# LSM303_breakout_board-v12.net
KiCad netlist of a schematic drawn in EAGLE
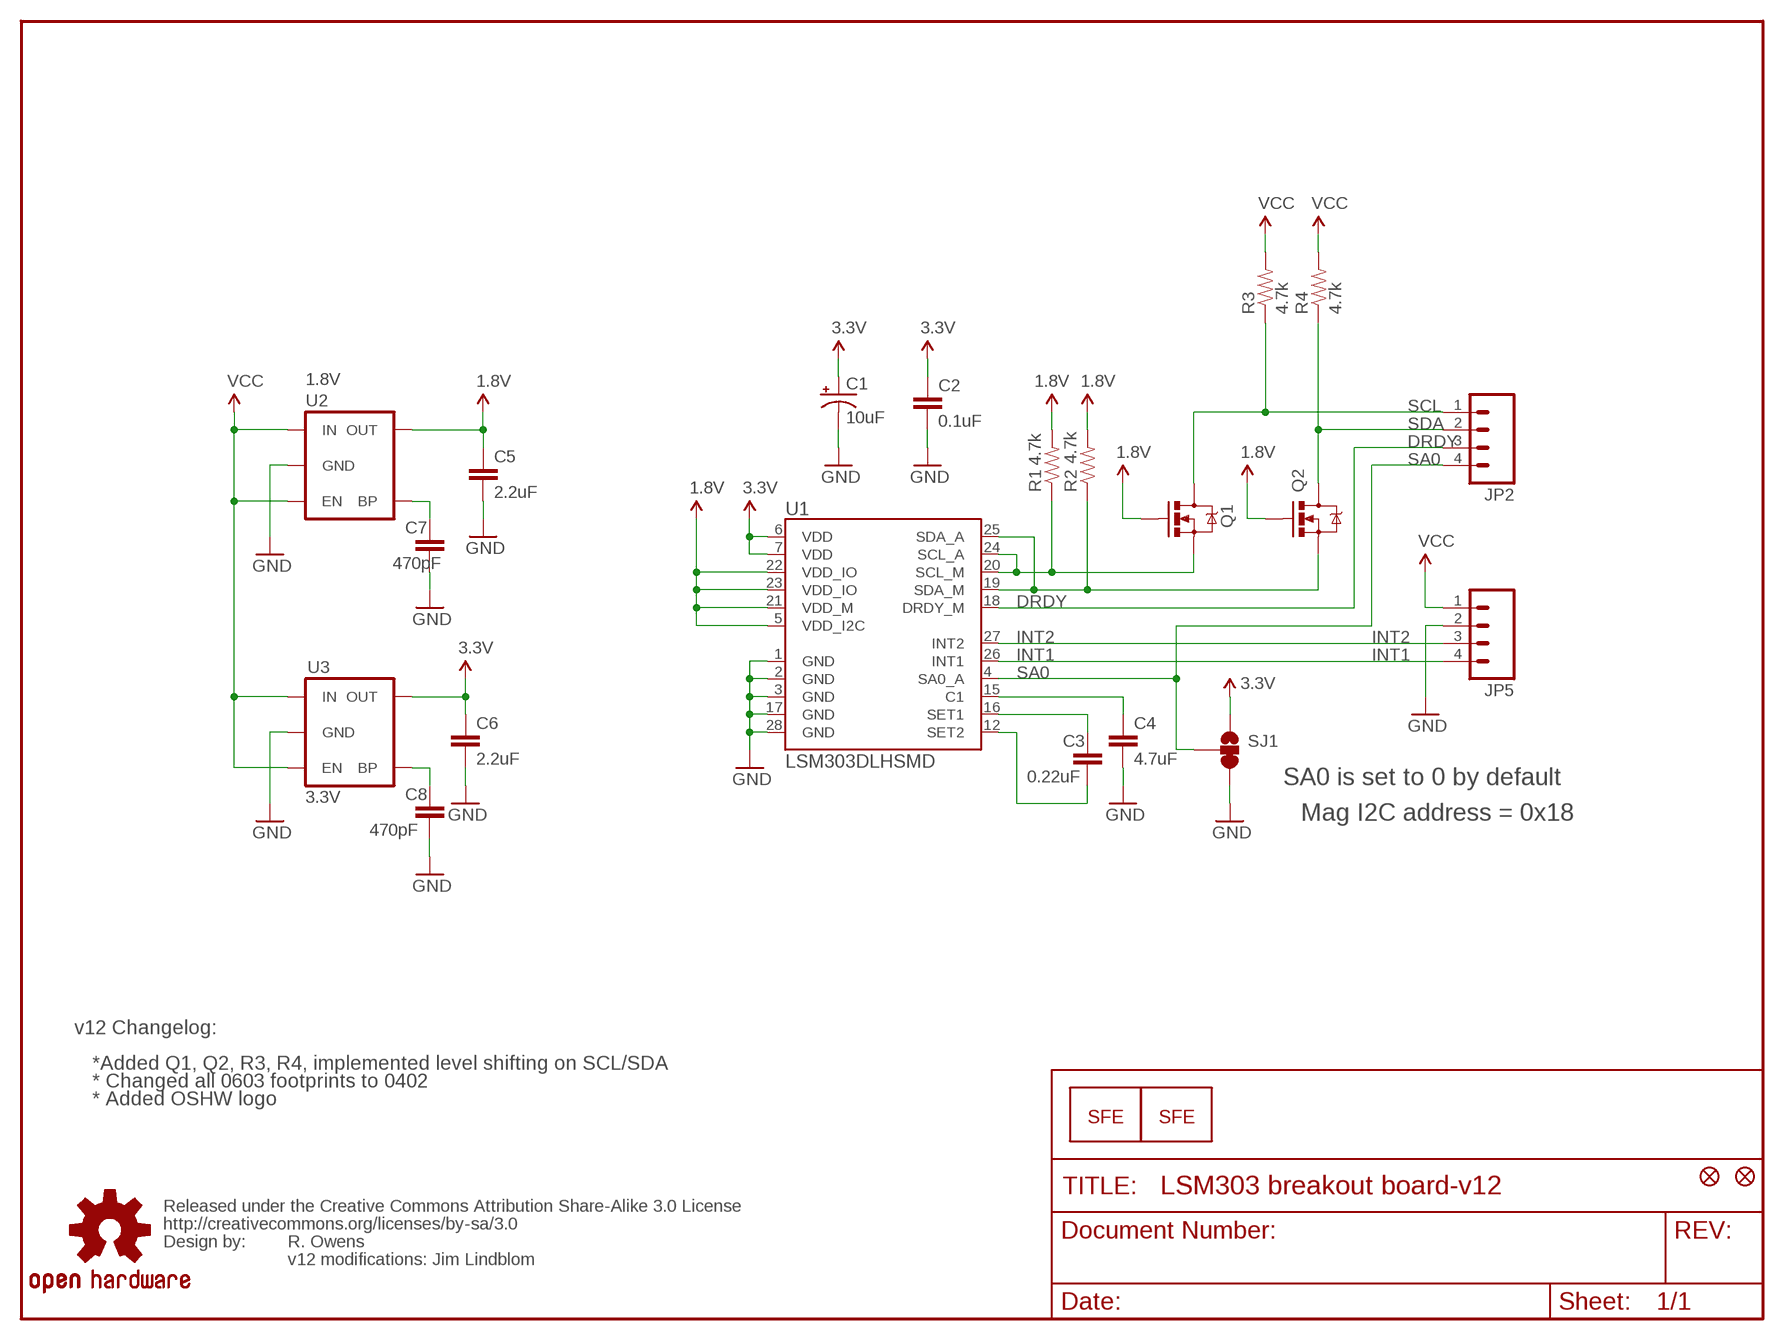
[diagram p0: schematic, sheet 1]

(export (version "E")
  (design (tool "Eeschema 10.0.6"))
  (components
    (comp (ref "C1")
      (value "10uF")
      (footprint "eagle-import:EIA3216")
      (libsource (lib "eagle-import") (part "CAP_POL1206"))
    )
    (comp (ref "C2")
      (value "0.1uF")
      (footprint "eagle-import:0402-CAP")
      (libsource (lib "eagle-import") (part "CAP0402-CAP"))
    )
    (comp (ref "C3")
      (value "0.22uF")
      (footprint "eagle-import:0402-CAP")
      (libsource (lib "eagle-import") (part "CAP0402-CAP"))
    )
    (comp (ref "C4")
      (value "4.7uF")
      (footprint "eagle-import:0402-CAP")
      (libsource (lib "eagle-import") (part "CAP0402-CAP"))
    )
    (comp (ref "C5")
      (value "2.2uF")
      (footprint "eagle-import:0402-CAP")
      (libsource (lib "eagle-import") (part "CAP0402-CAP"))
    )
    (comp (ref "C6")
      (value "2.2uF")
      (footprint "eagle-import:0402-CAP")
      (libsource (lib "eagle-import") (part "CAP0402-CAP"))
    )
    (comp (ref "C7")
      (value "470pF")
      (footprint "eagle-import:0402-CAP")
      (libsource (lib "eagle-import") (part "CAP0402-CAP"))
    )
    (comp (ref "C8")
      (value "470pF")
      (footprint "eagle-import:0402-CAP")
      (libsource (lib "eagle-import") (part "CAP0402-CAP"))
    )
    (comp (ref "JP1")
      (value "LOGO-SFENW2")
      (footprint "eagle-import:SFE-NEW-WEB")
      (libsource (lib "eagle-import") (part "LOGO-SFENW2"))
    )
    (comp (ref "JP2")
      (value "M04PTH")
      (footprint "eagle-import:1X04")
      (libsource (lib "eagle-import") (part "M04PTH"))
    )
    (comp (ref "JP3")
      (value "FIDUCIAL1X2")
      (footprint "eagle-import:FIDUCIAL-1X2")
      (libsource (lib "eagle-import") (part "FIDUCIAL1X2"))
    )
    (comp (ref "JP4")
      (value "FIDUCIAL1X2")
      (footprint "eagle-import:FIDUCIAL-1X2")
      (libsource (lib "eagle-import") (part "FIDUCIAL1X2"))
    )
    (comp (ref "JP5")
      (value "M04PTH")
      (footprint "eagle-import:1X04")
      (libsource (lib "eagle-import") (part "M04PTH"))
    )
    (comp (ref "JP6")
      (value "LOGO-SFESK")
      (footprint "eagle-import:SFE-LOGO-FLAME")
      (libsource (lib "eagle-import") (part "LOGO-SFESK"))
    )
    (comp (ref "Q1")
      (value "MOSFET-N-CH")
      (footprint "eagle-import:SOT23-3")
      (libsource (lib "eagle-import") (part "MOSFET-NCHANNELSMD"))
    )
    (comp (ref "Q2")
      (value "MOSFET-N-CH")
      (footprint "eagle-import:SOT23-3")
      (libsource (lib "eagle-import") (part "MOSFET-NCHANNELSMD"))
    )
    (comp (ref "R1")
      (value "4.7k")
      (footprint "eagle-import:0402-RES")
      (libsource (lib "eagle-import") (part "RESISTOR0402-RES"))
    )
    (comp (ref "R2")
      (value "4.7k")
      (footprint "eagle-import:0402-RES")
      (libsource (lib "eagle-import") (part "RESISTOR0402-RES"))
    )
    (comp (ref "R3")
      (value "4.7k")
      (footprint "eagle-import:0402-RES")
      (libsource (lib "eagle-import") (part "RESISTOR0402-RES"))
    )
    (comp (ref "R4")
      (value "4.7k")
      (footprint "eagle-import:0402-RES")
      (libsource (lib "eagle-import") (part "RESISTOR0402-RES"))
    )
    (comp (ref "SJ1")
      (value "SOLDERJUMPER_2WAYPASTE2&3")
      (footprint "eagle-import:SJ_3_PASTE2&3")
      (libsource (lib "eagle-import") (part "SOLDERJUMPER_2WAYPASTE2&3"))
    )
    (comp (ref "U$5")
      (value "CREATIVE_COMMONS")
      (footprint "eagle-import:CREATIVE_COMMONS")
      (libsource (lib "eagle-import") (part "CREATIVE_COMMONS"))
    )
    (comp (ref "U$8")
      (value "OSHW-LOGOS")
      (footprint "eagle-import:OSHW-LOGO-S")
      (libsource (lib "eagle-import") (part "OSHW-LOGOS"))
    )
    (comp (ref "U1")
      (value "LSM303DLHSMD")
      (footprint "eagle-import:LGA28-5X5")
      (libsource (lib "eagle-import") (part "LSM303DLHSMD"))
    )
    (comp (ref "U2")
      (value "1.8V")
      (footprint "eagle-import:SC70")
      (libsource (lib "eagle-import") (part "V_REG_LDOSMD2"))
    )
    (comp (ref "U3")
      (value "3.3V")
      (footprint "eagle-import:SOT23-5")
      (libsource (lib "eagle-import") (part "V_REG_LDOSMD"))
    )
  )
  (nets
    (net (code "1") (name "/DRDY") (class "Default")
      (node (ref "JP2") (pin "3") (pinfunction "3_3") (pintype "passive"))
      (node (ref "U1") (pin "18") (pinfunction "DRDY_M_18") (pintype "bidirectional"))
    )
    (net (code "2") (name "/INT1") (class "Default")
      (node (ref "JP5") (pin "4") (pinfunction "4_4") (pintype "passive"))
      (node (ref "U1") (pin "26") (pinfunction "INT1_26") (pintype "bidirectional"))
    )
    (net (code "3") (name "/INT2") (class "Default")
      (node (ref "JP5") (pin "3") (pinfunction "3_3") (pintype "passive"))
      (node (ref "U1") (pin "27") (pinfunction "INT2_27") (pintype "bidirectional"))
    )
    (net (code "4") (name "/SA0") (class "Default")
      (node (ref "JP2") (pin "4") (pinfunction "4_4") (pintype "passive"))
      (node (ref "SJ1") (pin "2") (pinfunction "2_2") (pintype "passive"))
      (node (ref "U1") (pin "4") (pinfunction "SA0_A_4") (pintype "bidirectional"))
    )
    (net (code "5") (name "/SCL") (class "Default")
      (node (ref "JP2") (pin "1") (pinfunction "1_1") (pintype "passive"))
      (node (ref "Q1") (pin "3") (pinfunction "D_3") (pintype "passive"))
      (node (ref "R3") (pin "1") (pinfunction "1_1") (pintype "passive"))
    )
    (net (code "6") (name "/SDA") (class "Default")
      (node (ref "JP2") (pin "2") (pinfunction "2_2") (pintype "passive"))
      (node (ref "Q2") (pin "3") (pinfunction "D_3") (pintype "passive"))
      (node (ref "R4") (pin "1") (pinfunction "1_1") (pintype "passive"))
    )
    (net (code "7") (name "1.8V") (class "Default")
      (node (ref "C5") (pin "1") (pinfunction "1_1") (pintype "passive"))
      (node (ref "Q1") (pin "1") (pinfunction "G_1") (pintype "passive"))
      (node (ref "Q2") (pin "1") (pinfunction "G_1") (pintype "passive"))
      (node (ref "R1") (pin "2") (pinfunction "2_2") (pintype "passive"))
      (node (ref "R2") (pin "2") (pinfunction "2_2") (pintype "passive"))
      (node (ref "U1") (pin "21") (pinfunction "VDD_M_21") (pintype "bidirectional"))
      (node (ref "U1") (pin "22") (pinfunction "VDD_IO_22") (pintype "bidirectional"))
      (node (ref "U1") (pin "23") (pinfunction "VDD_IO_23") (pintype "bidirectional"))
      (node (ref "U1") (pin "5") (pinfunction "VDD_I2C_5") (pintype "bidirectional"))
      (node (ref "U2") (pin "5") (pinfunction "OUT_5") (pintype "passive"))
    )
    (net (code "8") (name "3.3V") (class "Default")
      (node (ref "C1") (pin "A") (pinfunction "+_A") (pintype "passive"))
      (node (ref "C2") (pin "1") (pinfunction "1_1") (pintype "passive"))
      (node (ref "C6") (pin "1") (pinfunction "1_1") (pintype "passive"))
      (node (ref "SJ1") (pin "1") (pinfunction "1_1") (pintype "passive"))
      (node (ref "U1") (pin "6") (pinfunction "VDD_6") (pintype "bidirectional"))
      (node (ref "U1") (pin "7") (pinfunction "VDD_7") (pintype "bidirectional"))
      (node (ref "U3") (pin "5") (pinfunction "OUT_5") (pintype "passive"))
    )
    (net (code "9") (name "GND") (class "Default")
      (node (ref "C1") (pin "C") (pinfunction "-_C") (pintype "passive"))
      (node (ref "C2") (pin "2") (pinfunction "2_2") (pintype "passive"))
      (node (ref "C4") (pin "2") (pinfunction "2_2") (pintype "passive"))
      (node (ref "C5") (pin "2") (pinfunction "2_2") (pintype "passive"))
      (node (ref "C6") (pin "2") (pinfunction "2_2") (pintype "passive"))
      (node (ref "C7") (pin "2") (pinfunction "2_2") (pintype "passive"))
      (node (ref "C8") (pin "2") (pinfunction "2_2") (pintype "passive"))
      (node (ref "JP5") (pin "2") (pinfunction "2_2") (pintype "passive"))
      (node (ref "SJ1") (pin "3") (pinfunction "3_3") (pintype "passive"))
      (node (ref "U1") (pin "1") (pinfunction "GND_1") (pintype "bidirectional"))
      (node (ref "U1") (pin "17") (pinfunction "GND_17") (pintype "bidirectional"))
      (node (ref "U1") (pin "2") (pinfunction "GND_2") (pintype "bidirectional"))
      (node (ref "U1") (pin "28") (pinfunction "GND_28") (pintype "bidirectional"))
      (node (ref "U1") (pin "3") (pinfunction "GND_3") (pintype "bidirectional"))
      (node (ref "U2") (pin "2") (pinfunction "GND_2") (pintype "input"))
      (node (ref "U3") (pin "2") (pinfunction "GND_2") (pintype "input"))
    )
    (net (code "10") (name "Net-(Q1-S)") (class "Default")
      (node (ref "Q1") (pin "2") (pinfunction "S_2") (pintype "passive"))
      (node (ref "R1") (pin "1") (pinfunction "1_1") (pintype "passive"))
      (node (ref "U1") (pin "20") (pinfunction "SCL_M_20") (pintype "bidirectional"))
      (node (ref "U1") (pin "24") (pinfunction "SCL_A_24") (pintype "bidirectional"))
    )
    (net (code "11") (name "Net-(Q2-S)") (class "Default")
      (node (ref "Q2") (pin "2") (pinfunction "S_2") (pintype "passive"))
      (node (ref "R2") (pin "1") (pinfunction "1_1") (pintype "passive"))
      (node (ref "U1") (pin "19") (pinfunction "SDA_M_19") (pintype "bidirectional"))
      (node (ref "U1") (pin "25") (pinfunction "SDA_A_25") (pintype "bidirectional"))
    )
    (net (code "12") (name "Net-(U1-C1)") (class "Default")
      (node (ref "C4") (pin "1") (pinfunction "1_1") (pintype "passive"))
      (node (ref "U1") (pin "15") (pinfunction "C1_15") (pintype "bidirectional"))
    )
    (net (code "13") (name "Net-(U1-SET1)") (class "Default")
      (node (ref "C3") (pin "1") (pinfunction "1_1") (pintype "passive"))
      (node (ref "U1") (pin "16") (pinfunction "SET1_16") (pintype "bidirectional"))
    )
    (net (code "14") (name "Net-(U1-SET2)") (class "Default")
      (node (ref "C3") (pin "2") (pinfunction "2_2") (pintype "passive"))
      (node (ref "U1") (pin "12") (pinfunction "SET2_12") (pintype "bidirectional"))
    )
    (net (code "15") (name "Net-(U2-BP)") (class "Default")
      (node (ref "C7") (pin "1") (pinfunction "1_1") (pintype "passive"))
      (node (ref "U2") (pin "4") (pinfunction "BP_4") (pintype "input"))
    )
    (net (code "16") (name "Net-(U3-BP)") (class "Default")
      (node (ref "C8") (pin "1") (pinfunction "1_1") (pintype "passive"))
      (node (ref "U3") (pin "4") (pinfunction "BP_4") (pintype "input"))
    )
    (net (code "17") (name "VCC") (class "Default")
      (node (ref "JP5") (pin "1") (pinfunction "1_1") (pintype "passive"))
      (node (ref "R3") (pin "2") (pinfunction "2_2") (pintype "passive"))
      (node (ref "R4") (pin "2") (pinfunction "2_2") (pintype "passive"))
      (node (ref "U2") (pin "1") (pinfunction "IN_1") (pintype "input"))
      (node (ref "U2") (pin "3") (pinfunction "EN_3") (pintype "input"))
      (node (ref "U3") (pin "1") (pinfunction "IN_1") (pintype "input"))
      (node (ref "U3") (pin "3") (pinfunction "EN_3") (pintype "input"))
    )
  )
)
